# Actionneur.net
KiCad netlist of a schematic drawn in Altium Designer
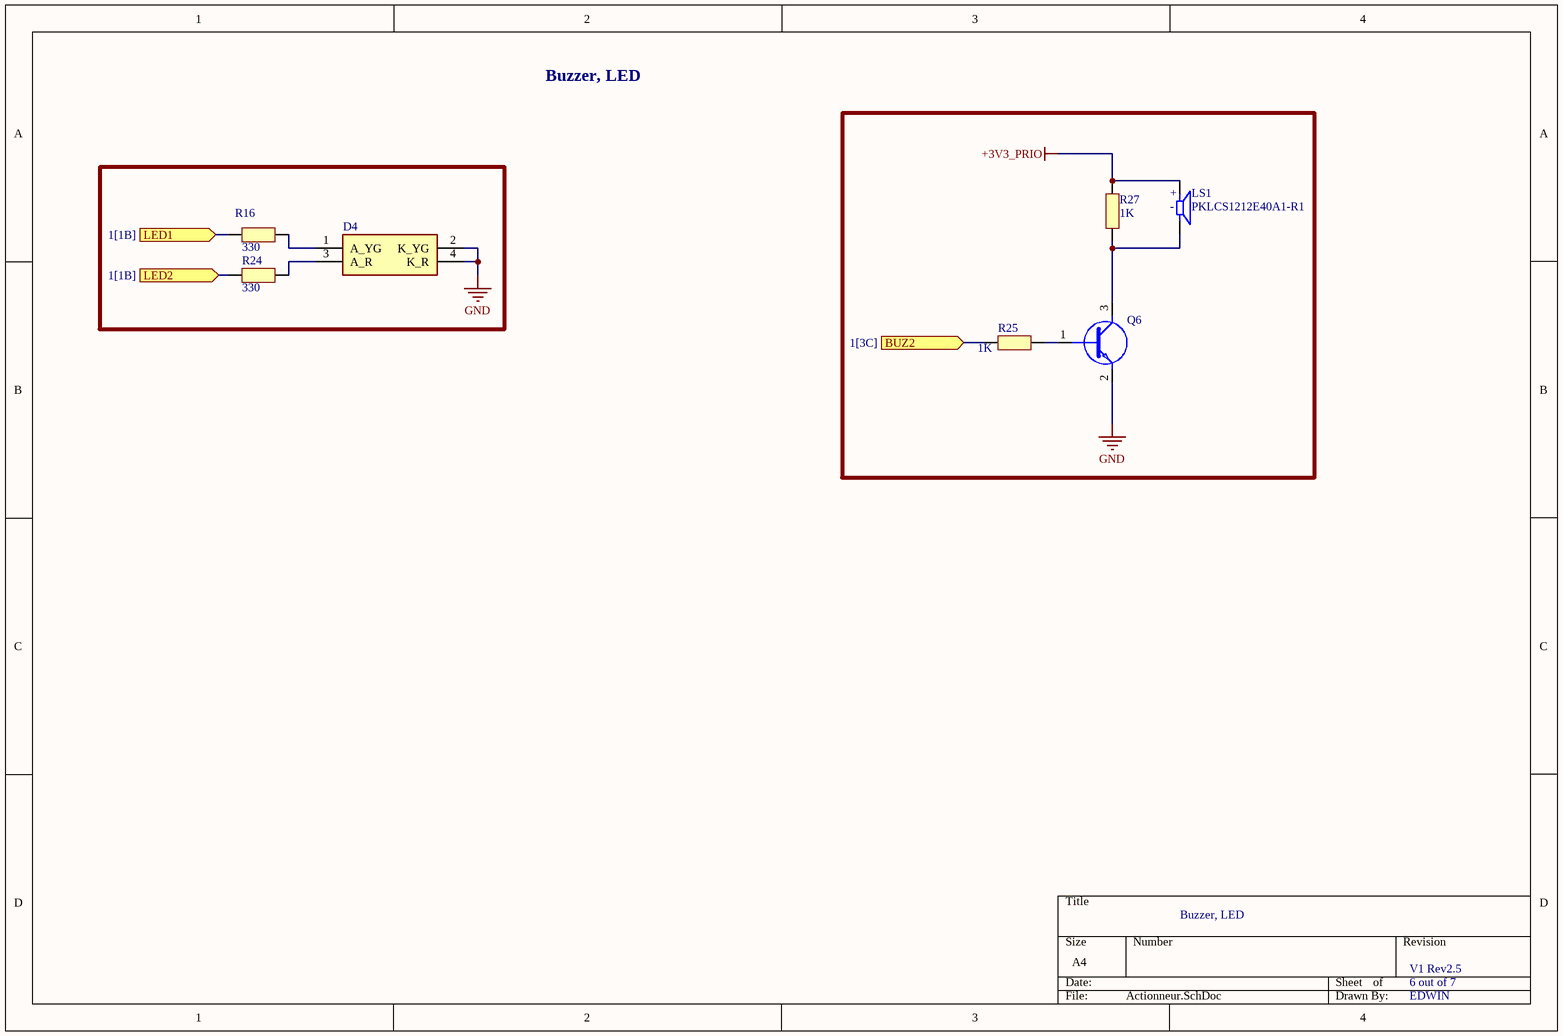
[diagram p0: Actionneur.SchDoc]

(export (version "E")
  (design (tool "Eeschema 10.0.6"))
  (components
    (comp (ref "D4")
      (value "598-8610-207F")
      (footprint "5988610207F")
      (description "Standard LEDs - SMD Red/Green WC 80/50mcd 645/570nm")
      (fields (field (name "MOUSER PART NUMBER") "645-598-8610-207F"))
      (libsource (lib "SCHLibrary") (part "598-8610-207F"))
    )
    (comp (ref "LS1")
      (value "PKLCS1212E40A1-R1")
      (footprint "SPKR_PKLCS1212E40A1-R1")
      (description "Buzzers Transducer, Externally Driven Piezo 1.5V 2kHz 70dB @ 1.5V, 10cm Surface Mount Solder Pads")
      (fields (field (name "MF") "Murata Electronics"))
      (libsource (lib "SCHLibrary") (part "PKLCS1212E40A1-R1"))
    )
    (comp (ref "Q6")
      (value "SS8050-G")
      (footprint "SS8050-G")
      (description "Bipolar Transistors - BJT NPN TRANSISTOR 1.5A 40V")
      (libsource (lib "SCHLibrary") (part "SS8050-G"))
    )
    (comp (ref "R16")
      (value "330")
      (footprint "RESC1005X06N")
      (libsource (lib "SCHLibrary") (part "Resistor"))
    )
    (comp (ref "R24")
      (value "330")
      (footprint "RESC1005X06N")
      (libsource (lib "SCHLibrary") (part "Resistor"))
    )
    (comp (ref "R25")
      (value "1K")
      (footprint "RESC1005X06N")
      (libsource (lib "SCHLibrary") (part "Resistor"))
    )
    (comp (ref "R27") (value "1K") (footprint "RESC1005X06N") (libsource (lib "") (part "Resistor_1")))
  )
  (nets
    (net (code "1") (name "+3V3_PRIO") (class "Default")
      (node (ref "LS1") (pin "P") (pinfunction "P_P") (pintype "passive"))
      (node (ref "R27") (pin "1") (pinfunction "1_1") (pintype "passive"))
    )
    (net (code "2") (name "/BUZ2") (class "Default")
      (node (ref "R25") (pin "2") (pinfunction "2_2") (pintype "passive"))
    )
    (net (code "3") (name "/LED1") (class "Default")
      (node (ref "R16") (pin "2") (pinfunction "2_2") (pintype "passive"))
    )
    (net (code "4") (name "/LED2") (class "Default")
      (node (ref "R24") (pin "2") (pinfunction "2_2") (pintype "passive"))
    )
    (net (code "5") (name "GND") (class "Default")
      (node (ref "D4") (pin "2") (pinfunction "K_YG_2") (pintype "passive"))
      (node (ref "D4") (pin "4") (pinfunction "K_R_4") (pintype "passive"))
      (node (ref "Q6") (pin "2") (pinfunction "E_2") (pintype "passive"))
    )
    (net (code "6") (name "Net-(D4-A_R)") (class "Default")
      (node (ref "D4") (pin "3") (pinfunction "A_R_3") (pintype "passive"))
      (node (ref "R24") (pin "1") (pinfunction "1_1") (pintype "passive"))
    )
    (net (code "7") (name "Net-(D4-A_YG)") (class "Default")
      (node (ref "D4") (pin "1") (pinfunction "A_YG_1") (pintype "passive"))
      (node (ref "R16") (pin "1") (pinfunction "1_1") (pintype "passive"))
    )
    (net (code "8") (name "Net-(Q6-B)") (class "Default")
      (node (ref "Q6") (pin "1") (pinfunction "B_1") (pintype "passive"))
      (node (ref "R25") (pin "1") (pinfunction "1_1") (pintype "passive"))
    )
    (net (code "9") (name "Net-(Q6-C)") (class "Default")
      (node (ref "LS1") (pin "N") (pinfunction "N_N") (pintype "passive"))
      (node (ref "Q6") (pin "3") (pinfunction "C_3") (pintype "passive"))
      (node (ref "R27") (pin "2") (pinfunction "2_2") (pintype "passive"))
    )
  )
)
